# domus-silicea_-_M1_-_Arduino_Pro-Mini.net
KiCad netlist of a schematic drawn in EAGLE
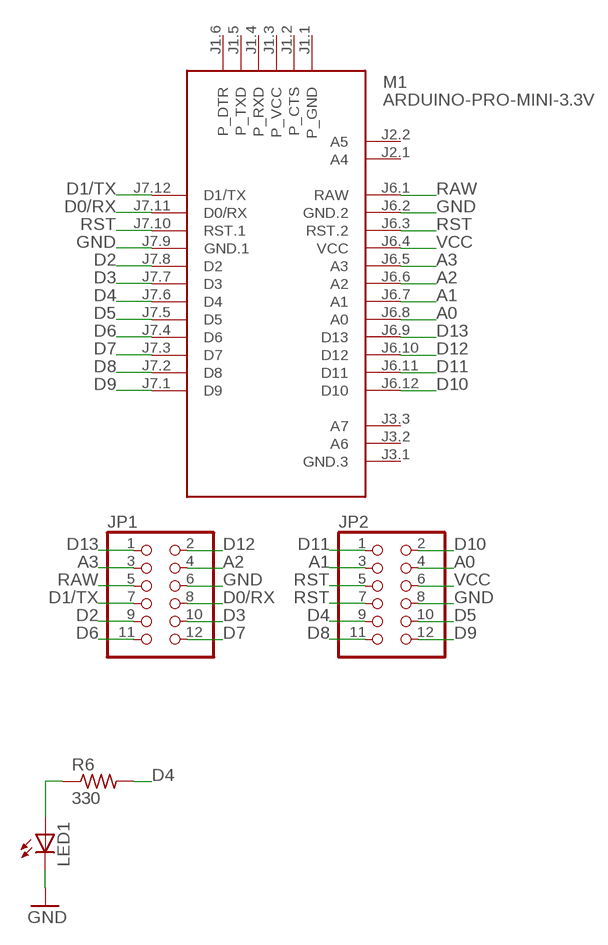
[diagram p0: schematic, sheet 1]

(export (version "E")
  (design (tool "Eeschema 10.0.6"))
  (components
    (comp (ref "JP1")
      (value "PINHD-2X6")
      (footprint "eagle-import:2X06")
      (libsource (lib "eagle-import") (part "PINHD-2X6"))
    )
    (comp (ref "JP2")
      (value "PINHD-2X6")
      (footprint "eagle-import:2X06")
      (libsource (lib "eagle-import") (part "PINHD-2X6"))
    )
    (comp (ref "LED1")
      (value "LED5MM")
      (footprint "eagle-import:LED5MM")
      (libsource (lib "eagle-import") (part "LED5MM"))
    )
    (comp (ref "M1")
      (value "ARDUINO-PRO-MINI-3.3V")
      (footprint "eagle-import:ARDUINO-PRO-MINI")
      (libsource (lib "eagle-import") (part "ARDUINO-PRO-MINI-3.3V"))
    )
    (comp (ref "R6")
      (value "330")
      (footprint "eagle-import:0204_7")
      (libsource (lib "eagle-import") (part "R-US_0204/7"))
    )
  )
  (nets
    (net (code "1") (name "/A0") (class "Default")
      (node (ref "JP2") (pin "4") (pinfunction "4_4") (pintype "passive"))
      (node (ref "M1") (pin "J6.8") (pinfunction "A0_J6.8") (pintype "bidirectional"))
    )
    (net (code "2") (name "/A1") (class "Default")
      (node (ref "JP2") (pin "3") (pinfunction "3_3") (pintype "passive"))
      (node (ref "M1") (pin "J6.7") (pinfunction "A1_J6.7") (pintype "bidirectional"))
    )
    (net (code "3") (name "/A2") (class "Default")
      (node (ref "JP1") (pin "4") (pinfunction "4_4") (pintype "passive"))
      (node (ref "M1") (pin "J6.6") (pinfunction "A2_J6.6") (pintype "bidirectional"))
    )
    (net (code "4") (name "/A3") (class "Default")
      (node (ref "JP1") (pin "3") (pinfunction "3_3") (pintype "passive"))
      (node (ref "M1") (pin "J6.5") (pinfunction "A3_J6.5") (pintype "bidirectional"))
    )
    (net (code "5") (name "/D0{slash}RX") (class "Default")
      (node (ref "JP1") (pin "8") (pinfunction "8_8") (pintype "passive"))
      (node (ref "M1") (pin "J7.11") (pinfunction "D0/RX_J7.11") (pintype "bidirectional"))
    )
    (net (code "6") (name "/D1{slash}TX") (class "Default")
      (node (ref "JP1") (pin "7") (pinfunction "7_7") (pintype "passive"))
      (node (ref "M1") (pin "J7.12") (pinfunction "D1/TX_J7.12") (pintype "bidirectional"))
    )
    (net (code "7") (name "/D2") (class "Default")
      (node (ref "JP1") (pin "9") (pinfunction "9_9") (pintype "passive"))
      (node (ref "M1") (pin "J7.8") (pinfunction "D2_J7.8") (pintype "bidirectional"))
    )
    (net (code "8") (name "/D3") (class "Default")
      (node (ref "JP1") (pin "10") (pinfunction "10_10") (pintype "passive"))
      (node (ref "M1") (pin "J7.7") (pinfunction "D3_J7.7") (pintype "bidirectional"))
    )
    (net (code "9") (name "/D4") (class "Default")
      (node (ref "JP2") (pin "9") (pinfunction "9_9") (pintype "passive"))
      (node (ref "M1") (pin "J7.6") (pinfunction "D4_J7.6") (pintype "bidirectional"))
      (node (ref "R6") (pin "2") (pinfunction "2_2") (pintype "passive"))
    )
    (net (code "10") (name "/D5") (class "Default")
      (node (ref "JP2") (pin "10") (pinfunction "10_10") (pintype "passive"))
      (node (ref "M1") (pin "J7.5") (pinfunction "D5_J7.5") (pintype "bidirectional"))
    )
    (net (code "11") (name "/D6") (class "Default")
      (node (ref "JP1") (pin "11") (pinfunction "11_11") (pintype "passive"))
      (node (ref "M1") (pin "J7.4") (pinfunction "D6_J7.4") (pintype "bidirectional"))
    )
    (net (code "12") (name "/D7") (class "Default")
      (node (ref "JP1") (pin "12") (pinfunction "12_12") (pintype "passive"))
      (node (ref "M1") (pin "J7.3") (pinfunction "D7_J7.3") (pintype "bidirectional"))
    )
    (net (code "13") (name "/D8") (class "Default")
      (node (ref "JP2") (pin "11") (pinfunction "11_11") (pintype "passive"))
      (node (ref "M1") (pin "J7.2") (pinfunction "D8_J7.2") (pintype "bidirectional"))
    )
    (net (code "14") (name "/D9") (class "Default")
      (node (ref "JP2") (pin "12") (pinfunction "12_12") (pintype "passive"))
      (node (ref "M1") (pin "J7.1") (pinfunction "D9_J7.1") (pintype "bidirectional"))
    )
    (net (code "15") (name "/D10") (class "Default")
      (node (ref "JP2") (pin "2") (pinfunction "2_2") (pintype "passive"))
      (node (ref "M1") (pin "J6.12") (pinfunction "D10_J6.12") (pintype "bidirectional"))
    )
    (net (code "16") (name "/D11") (class "Default")
      (node (ref "JP2") (pin "1") (pinfunction "1_1") (pintype "passive"))
      (node (ref "M1") (pin "J6.11") (pinfunction "D11_J6.11") (pintype "bidirectional"))
    )
    (net (code "17") (name "/D12") (class "Default")
      (node (ref "JP1") (pin "2") (pinfunction "2_2") (pintype "passive"))
      (node (ref "M1") (pin "J6.10") (pinfunction "D12_J6.10") (pintype "bidirectional"))
    )
    (net (code "18") (name "/D13") (class "Default")
      (node (ref "JP1") (pin "1") (pinfunction "1_1") (pintype "passive"))
      (node (ref "M1") (pin "J6.9") (pinfunction "D13_J6.9") (pintype "bidirectional"))
    )
    (net (code "19") (name "/RAW") (class "Default")
      (node (ref "JP1") (pin "5") (pinfunction "5_5") (pintype "passive"))
      (node (ref "M1") (pin "J6.1") (pinfunction "RAW_J6.1") (pintype "power_in"))
    )
    (net (code "20") (name "/RST") (class "Default")
      (node (ref "JP2") (pin "5") (pinfunction "5_5") (pintype "passive"))
      (node (ref "JP2") (pin "7") (pinfunction "7_7") (pintype "passive"))
      (node (ref "M1") (pin "J6.3") (pinfunction "RST.2_J6.3") (pintype "bidirectional"))
      (node (ref "M1") (pin "J7.10") (pinfunction "RST.1_J7.10") (pintype "bidirectional"))
    )
    (net (code "21") (name "/VCC") (class "Default")
      (node (ref "JP2") (pin "6") (pinfunction "6_6") (pintype "passive"))
      (node (ref "M1") (pin "J6.4") (pinfunction "VCC_J6.4") (pintype "power_in"))
    )
    (net (code "22") (name "GND") (class "Default")
      (node (ref "JP1") (pin "6") (pinfunction "6_6") (pintype "passive"))
      (node (ref "JP2") (pin "8") (pinfunction "8_8") (pintype "passive"))
      (node (ref "LED1") (pin "K") (pinfunction "C_K") (pintype "passive"))
      (node (ref "M1") (pin "J6.2") (pinfunction "GND.2_J6.2") (pintype "power_in"))
      (node (ref "M1") (pin "J7.9") (pinfunction "GND.1_J7.9") (pintype "power_in"))
    )
    (net (code "23") (name "Net-(LED1-PadA)") (class "Default")
      (node (ref "LED1") (pin "A") (pinfunction "A_A") (pintype "passive"))
      (node (ref "R6") (pin "1") (pinfunction "1_1") (pintype "passive"))
    )
    (net (code "24") (name "unconnected-(M1-A4-PadJ2.1)") (class "Default")
      (node (ref "M1") (pin "J2.1") (pinfunction "A4_J2.1") (pintype "bidirectional"))
    )
    (net (code "25") (name "unconnected-(M1-A5-PadJ2.2)") (class "Default")
      (node (ref "M1") (pin "J2.2") (pinfunction "A5_J2.2") (pintype "bidirectional"))
    )
    (net (code "26") (name "unconnected-(M1-A6-PadJ3.2)") (class "Default")
      (node (ref "M1") (pin "J3.2") (pinfunction "A6_J3.2") (pintype "bidirectional"))
    )
    (net (code "27") (name "unconnected-(M1-A7-PadJ3.3)") (class "Default")
      (node (ref "M1") (pin "J3.3") (pinfunction "A7_J3.3") (pintype "bidirectional"))
    )
    (net (code "28") (name "unconnected-(M1-GND.3-PadJ3.1)") (class "Default")
      (node (ref "M1") (pin "J3.1") (pinfunction "GND.3_J3.1") (pintype "bidirectional"))
    )
    (net (code "29") (name "unconnected-(M1-P_CTS-PadJ1.2)") (class "Default")
      (node (ref "M1") (pin "J1.2") (pinfunction "P_CTS_J1.2") (pintype "bidirectional"))
    )
    (net (code "30") (name "unconnected-(M1-P_DTR-PadJ1.6)") (class "Default")
      (node (ref "M1") (pin "J1.6") (pinfunction "P_DTR_J1.6") (pintype "bidirectional"))
    )
    (net (code "31") (name "unconnected-(M1-P_GND-PadJ1.1)") (class "Default")
      (node (ref "M1") (pin "J1.1") (pinfunction "P_GND_J1.1") (pintype "bidirectional"))
    )
    (net (code "32") (name "unconnected-(M1-P_RXD-PadJ1.4)") (class "Default")
      (node (ref "M1") (pin "J1.4") (pinfunction "P_RXD_J1.4") (pintype "bidirectional"))
    )
    (net (code "33") (name "unconnected-(M1-P_TXD-PadJ1.5)") (class "Default")
      (node (ref "M1") (pin "J1.5") (pinfunction "P_TXD_J1.5") (pintype "bidirectional"))
    )
    (net (code "34") (name "unconnected-(M1-P_VCC-PadJ1.3)") (class "Default")
      (node (ref "M1") (pin "J1.3") (pinfunction "P_VCC_J1.3") (pintype "bidirectional"))
    )
  )
)
